# cooler.net
KiCad netlist of a schematic drawn in EAGLE
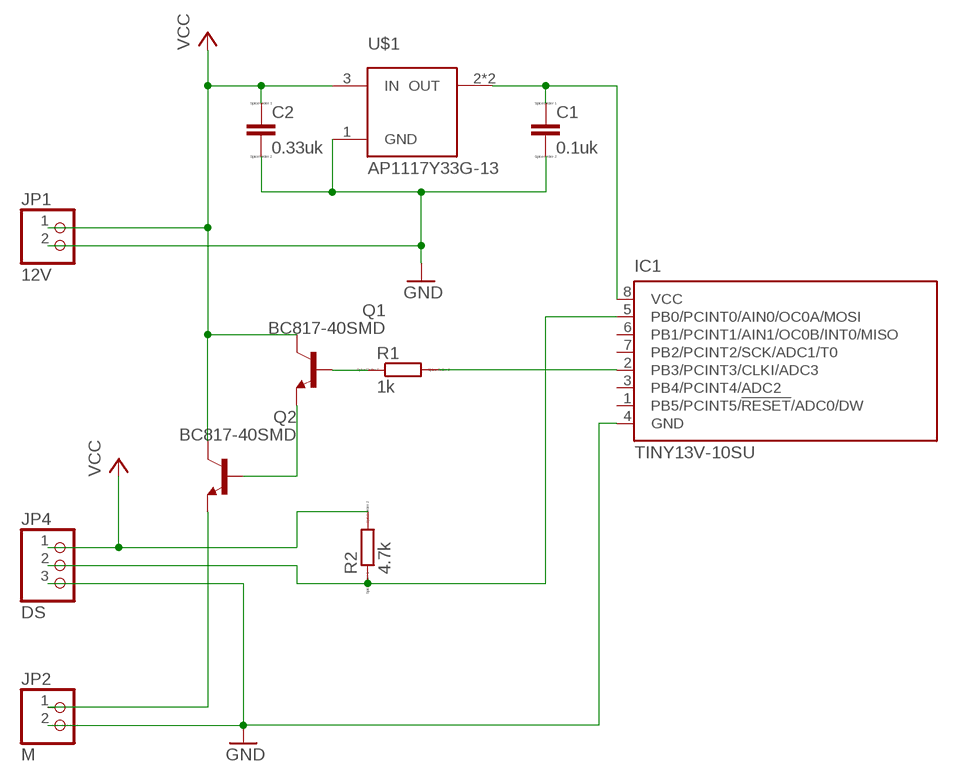
[diagram p0: schematic, sheet 1]

(export (version "E")
  (design (tool "Eeschema 10.0.6"))
  (components
    (comp (ref "C1")
      (value "0.1uk")
      (footprint "eagle-import:C0805")
      (libsource (lib "eagle-import") (part "C"))
    )
    (comp (ref "C2")
      (value "0.33uk")
      (footprint "eagle-import:C0805")
      (libsource (lib "eagle-import") (part "C"))
    )
    (comp (ref "IC1")
      (value "TINY13V-10SU")
      (footprint "eagle-import:8S2")
      (fields (field (name "MPN") "ATTINY13V-10SU"))
      (libsource (lib "eagle-import") (part "TINY13SUV-10"))
    )
    (comp (ref "JP1")
      (value "12V")
      (footprint "eagle-import:1X02_90")
      (libsource (lib "eagle-import") (part "PINHD-1X2/90"))
    )
    (comp (ref "JP2")
      (value "M")
      (footprint "eagle-import:1X02_90")
      (libsource (lib "eagle-import") (part "PINHD-1X2/90"))
    )
    (comp (ref "JP4")
      (value "DS")
      (footprint "eagle-import:1X03_90")
      (libsource (lib "eagle-import") (part "PINHD-1X3/90"))
    )
    (comp (ref "Q1")
      (value "BC817-40SMD")
      (footprint "eagle-import:SOT23-BEC")
      (libsource (lib "eagle-import") (part "BC817SMD-40"))
    )
    (comp (ref "Q2")
      (value "BC817-40SMD")
      (footprint "eagle-import:SOT23-BEC")
      (libsource (lib "eagle-import") (part "BC817SMD-40"))
    )
    (comp (ref "R1")
      (value "1k")
      (footprint "eagle-import:R0805")
      (libsource (lib "eagle-import") (part "R"))
    )
    (comp (ref "R2")
      (value "4.7k")
      (footprint "eagle-import:R0805")
      (libsource (lib "eagle-import") (part "R"))
    )
    (comp (ref "U$1")
      (value "AP1117Y33G-13")
      (footprint "eagle-import:SOT89")
      (libsource (lib "eagle-import") (part "AP1117Y33G-13"))
    )
  )
  (nets
    (net (code "1") (name "GND") (class "Default")
      (node (ref "C1") (pin "2") (pinfunction "2_2") (pintype "passive"))
      (node (ref "C2") (pin "2") (pinfunction "2_2") (pintype "passive"))
      (node (ref "IC1") (pin "4") (pinfunction "GND_4") (pintype "power_in"))
      (node (ref "JP1") (pin "2") (pinfunction "2_2") (pintype "passive"))
      (node (ref "JP2") (pin "2") (pinfunction "2_2") (pintype "passive"))
      (node (ref "JP4") (pin "3") (pinfunction "3_3") (pintype "passive"))
      (node (ref "U$1") (pin "1") (pinfunction "GND_1") (pintype "bidirectional"))
    )
    (net (code "2") (name "Net-(IC1-PB0{slash}PCINT0{slash}AIN0{slash}OC0A{slash}MOSI)") (class "Default")
      (node (ref "IC1") (pin "5") (pinfunction "PB0/PCINT0/AIN0/OC0A/MOSI_5") (pintype "bidirectional"))
      (node (ref "JP4") (pin "2") (pinfunction "2_2") (pintype "passive"))
      (node (ref "R2") (pin "1") (pinfunction "1_1") (pintype "passive"))
    )
    (net (code "3") (name "Net-(IC1-PB3{slash}PCINT3{slash}CLKI{slash}ADC3)") (class "Default")
      (node (ref "IC1") (pin "2") (pinfunction "PB3/PCINT3/CLKI/ADC3_2") (pintype "bidirectional"))
      (node (ref "R1") (pin "2") (pinfunction "2_2") (pintype "passive"))
    )
    (net (code "4") (name "Net-(IC1-VCC)") (class "Default")
      (node (ref "C1") (pin "1") (pinfunction "1_1") (pintype "passive"))
      (node (ref "IC1") (pin "8") (pinfunction "VCC_8") (pintype "power_in"))
      (node (ref "U$1") (pin "2") (pinfunction "OUT_2") (pintype "bidirectional"))
      (node (ref "U$1") (pin "2@1") (pinfunction "OUT_2@1") (pintype "bidirectional"))
    )
    (net (code "5") (name "Net-(JP2-Pad1)") (class "Default")
      (node (ref "JP2") (pin "1") (pinfunction "1_1") (pintype "passive"))
      (node (ref "Q2") (pin "E") (pinfunction "E_E") (pintype "passive"))
    )
    (net (code "6") (name "Net-(Q1-PadB)") (class "Default")
      (node (ref "Q1") (pin "B") (pinfunction "B_B") (pintype "passive"))
      (node (ref "R1") (pin "1") (pinfunction "1_1") (pintype "passive"))
    )
    (net (code "7") (name "Net-(Q1-PadE)") (class "Default")
      (node (ref "Q1") (pin "E") (pinfunction "E_E") (pintype "passive"))
      (node (ref "Q2") (pin "B") (pinfunction "B_B") (pintype "passive"))
    )
    (net (code "8") (name "VCC") (class "Default")
      (node (ref "C2") (pin "1") (pinfunction "1_1") (pintype "passive"))
      (node (ref "JP1") (pin "1") (pinfunction "1_1") (pintype "passive"))
      (node (ref "JP4") (pin "1") (pinfunction "1_1") (pintype "passive"))
      (node (ref "Q1") (pin "C") (pinfunction "C_C") (pintype "passive"))
      (node (ref "Q2") (pin "C") (pinfunction "C_C") (pintype "passive"))
      (node (ref "R2") (pin "2") (pinfunction "2_2") (pintype "passive"))
      (node (ref "U$1") (pin "3") (pinfunction "IN_3") (pintype "bidirectional"))
    )
    (net (code "9") (name "unconnected-(IC1-PB1{slash}PCINT1{slash}AIN1{slash}OC0B{slash}INT0{slash}MISO-Pad6)") (class "Default")
      (node (ref "IC1") (pin "6") (pinfunction "PB1/PCINT1/AIN1/OC0B/INT0/MISO_6") (pintype "bidirectional"))
    )
    (net (code "10") (name "unconnected-(IC1-PB2{slash}PCINT2{slash}SCK{slash}ADC1{slash}T0-Pad7)") (class "Default")
      (node (ref "IC1") (pin "7") (pinfunction "PB2/PCINT2/SCK/ADC1/T0_7") (pintype "bidirectional"))
    )
    (net (code "11") (name "unconnected-(IC1-PB4{slash}PCINT4{slash}ADC2-Pad3)") (class "Default")
      (node (ref "IC1") (pin "3") (pinfunction "PB4/PCINT4/ADC2_3") (pintype "bidirectional"))
    )
    (net (code "12") (name "unconnected-(IC1-PB5{slash}PCINT5{slash}~{RESET}{slash}ADC0{slash}DW-Pad1)") (class "Default")
      (node (ref "IC1") (pin "1") (pinfunction "PB5/PCINT5/~{RESET}/ADC0/DW_1") (pintype "bidirectional"))
    )
  )
)
